# 08_USB_To_UART.net
KiCad netlist of a schematic drawn in Altium Designer
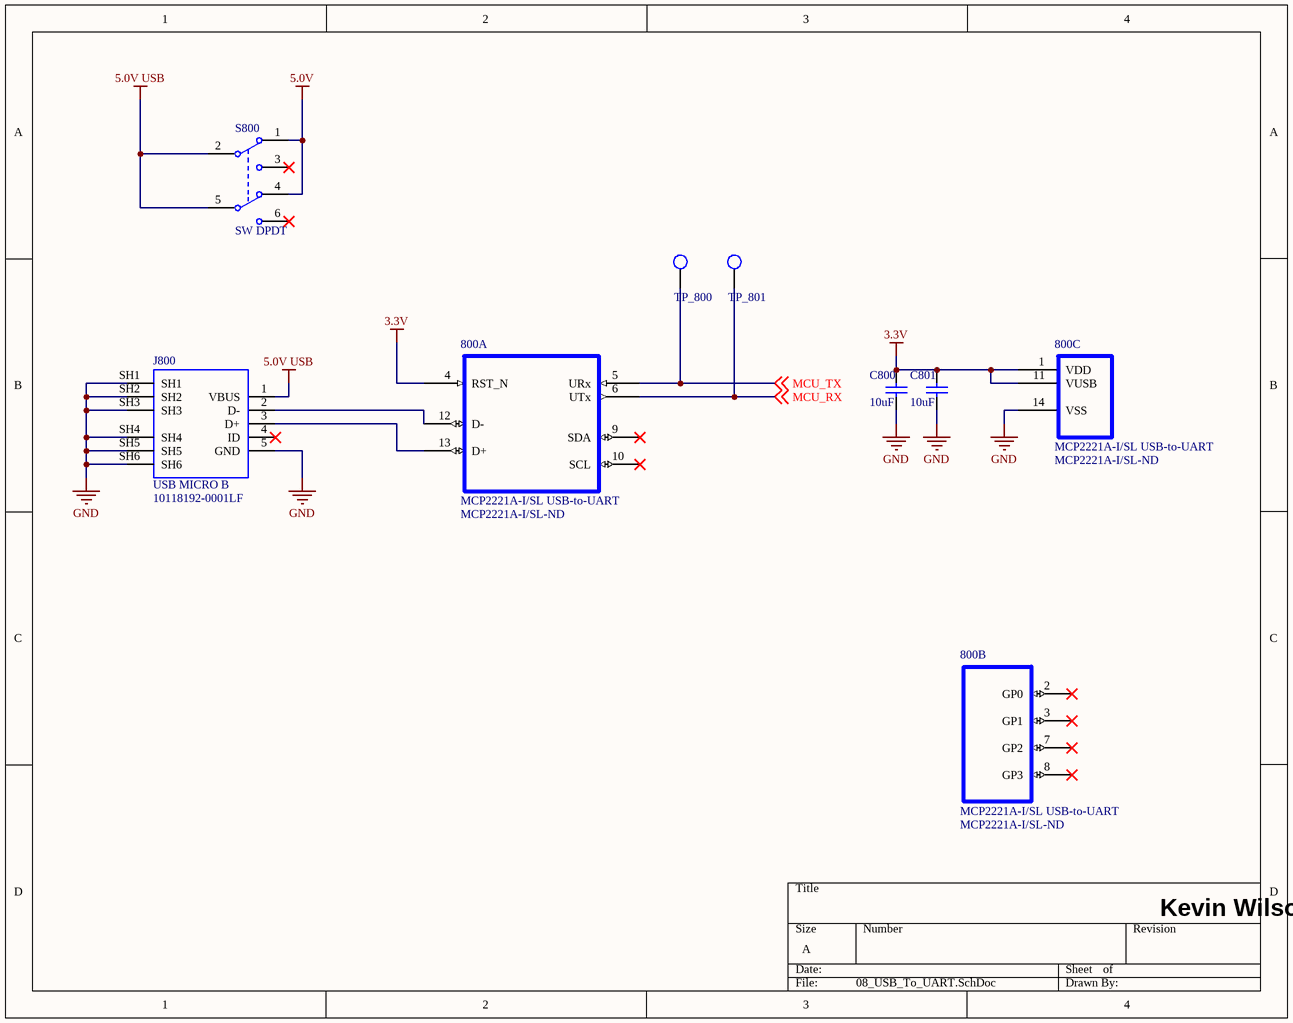
[diagram p0: 08_USB_To_UART.SchDoc]

(export (version "E")
  (design (tool "Eeschema 10.0.6"))
  (components
    (comp (ref "800")
      (value "MCP2221A-I/SL USB-to-UART")
      (footprint "IC_ MCP2221")
      (fields
        (field (name "MANUFACTURER") "Microchip")
        (field (name "MANUFACTURER PART NUMBER") "MCP2221A-I/SL")
        (field (name "SUPPLIER PART NUMBER 1") "MCP2221A-I/SL-ND")
      )
      (libsource (lib "ece315") (part "MCP2221A-I/SL USB-to-UART"))
    )
    (comp (ref "C800")
      (value "10uF")
      (footprint "CAP_0805")
      (description "CAP CER 10UF 16V X5R 0805")
      (fields
        (field (name "MANUFACTURER") "Samsung")
        (field (name "MANUFACTURER PART NUMBER") "CL21A106KOFNNNE")
      )
      (libsource (lib "ece315") (part "CAP_0805_U_010.00"))
    )
    (comp (ref "C801")
      (value "10uF")
      (footprint "CAP_0805")
      (description "CAP CER 10UF 16V X5R 0805")
      (fields
        (field (name "MANUFACTURER") "Samsung")
        (field (name "MANUFACTURER PART NUMBER") "CL21A106KOFNNNE")
      )
      (libsource (lib "ece315") (part "CAP_0805_U_010.00"))
    )
    (comp (ref "J800")
      (value "10118192-0001LF")
      (footprint "FCI_10118192")
      (description "CONN USB MICRO B RECPT SMT R/A")
      (fields
        (field (name "TOLERANCE") "USB MICRO B")
        (field (name "Comment") "CONN_RECP_FCI_10118192-0001LF.1")
      )
      (libsource (lib "ece315") (part "CONN_RECP_FCI_10118192-0001LF.1"))
    )
    (comp (ref "S800")
      (value "SW DPDT")
      (footprint "DPDT")
      (description "Switch")
      (fields
        (field (name "MANUFACTURER") "ITT /  C&K Components")
        (field (name "MANUFACTURER PART NUMBER") "JS202011SCQN")
        (field (name "PUBLISHER") "Altium Limited")
      )
      (libsource (lib "ece315") (part "SW DPDT"))
    )
    (comp (ref "TP_800")
      (value "TP_1206")
      (footprint "TP-SMC-1206")
      (description "Test Point SMD 1206")
      (fields
        (field (name "MANUFACTURER") "TE Connectivity (Tyco Electronics)")
        (field (name "MANUFACTURER PART NUMBER") "1625854-1")
      )
      (libsource (lib "ece315") (part "TP_1206"))
    )
    (comp (ref "TP_801")
      (value "TP_1206")
      (footprint "TP-SMC-1206")
      (description "Test Point SMD 1206")
      (fields
        (field (name "MANUFACTURER") "TE Connectivity (Tyco Electronics)")
        (field (name "MANUFACTURER PART NUMBER") "1625854-1")
      )
      (libsource (lib "ece315") (part "TP_1206"))
    )
  )
  (nets
    (net (code "1") (name "3.3V") (class "Default")
      (node (ref "800") (pin "1") (pinfunction "VDD_1") (pintype "power_in"))
      (node (ref "800") (pin "11") (pinfunction "VUSB_11") (pintype "power_in"))
      (node (ref "800") (pin "4") (pinfunction "RST_N_4") (pintype "input"))
      (node (ref "C800") (pin "2") (pinfunction "2_2") (pintype "passive"))
      (node (ref "C801") (pin "2") (pinfunction "2_2") (pintype "passive"))
    )
    (net (code "2") (name "5.0V") (class "Default")
      (node (ref "S800") (pin "1") (pinfunction "NC1_1") (pintype "passive"))
      (node (ref "S800") (pin "4") (pinfunction "NC2_4") (pintype "passive"))
    )
    (net (code "3") (name "5.0V USB") (class "Default")
      (node (ref "J800") (pin "1") (pinfunction "VBUS_1") (pintype "passive"))
      (node (ref "S800") (pin "2") (pinfunction "COMMON1_2") (pintype "passive"))
      (node (ref "S800") (pin "5") (pinfunction "COMMON2_5") (pintype "passive"))
    )
    (net (code "4") (name "GND") (class "Default")
      (node (ref "800") (pin "14") (pinfunction "VSS_14") (pintype "power_in"))
      (node (ref "C800") (pin "1") (pinfunction "1_1") (pintype "passive"))
      (node (ref "C801") (pin "1") (pinfunction "1_1") (pintype "passive"))
      (node (ref "J800") (pin "5") (pinfunction "GND_5") (pintype "passive"))
      (node (ref "J800") (pin "SH1") (pinfunction "SH1_SH1") (pintype "passive"))
      (node (ref "J800") (pin "SH2") (pinfunction "SH2_SH2") (pintype "passive"))
      (node (ref "J800") (pin "SH3") (pinfunction "SH3_SH3") (pintype "passive"))
      (node (ref "J800") (pin "SH4") (pinfunction "SH4_SH4") (pintype "passive"))
      (node (ref "J800") (pin "SH5") (pinfunction "SH5_SH5") (pintype "passive"))
      (node (ref "J800") (pin "SH6") (pinfunction "SH6_SH6") (pintype "passive"))
    )
    (net (code "5") (name "MCU_RX") (class "Default")
      (node (ref "800") (pin "6") (pinfunction "UTx_6") (pintype "output"))
      (node (ref "TP_801") (pin "1") (pintype "passive"))
    )
    (net (code "6") (name "MCU_TX") (class "Default")
      (node (ref "800") (pin "5") (pinfunction "URx_5") (pintype "input"))
      (node (ref "TP_800") (pin "1") (pintype "passive"))
    )
    (net (code "7") (name "Net-(800A-D+)") (class "Default")
      (node (ref "800") (pin "13") (pinfunction "D+_13") (pintype "bidirectional"))
      (node (ref "J800") (pin "3") (pinfunction "D+_3") (pintype "passive"))
    )
    (net (code "8") (name "Net-(800A-D-)") (class "Default")
      (node (ref "800") (pin "12") (pinfunction "D-_12") (pintype "bidirectional"))
      (node (ref "J800") (pin "2") (pinfunction "D-_2") (pintype "passive"))
    )
    (net (code "9") (name "unconnected-(800A-SCL-Pad10)") (class "Default")
      (node (ref "800") (pin "10") (pinfunction "SCL_10") (pintype "bidirectional+no_connect"))
    )
    (net (code "10") (name "unconnected-(800A-SDA-Pad9)") (class "Default")
      (node (ref "800") (pin "9") (pinfunction "SDA_9") (pintype "bidirectional+no_connect"))
    )
    (net (code "11") (name "unconnected-(800B-GP0-Pad2)") (class "Default")
      (node (ref "800") (pin "2") (pinfunction "GP0_2") (pintype "bidirectional+no_connect"))
    )
    (net (code "12") (name "unconnected-(800B-GP1-Pad3)") (class "Default")
      (node (ref "800") (pin "3") (pinfunction "GP1_3") (pintype "bidirectional+no_connect"))
    )
    (net (code "13") (name "unconnected-(800B-GP2-Pad7)") (class "Default")
      (node (ref "800") (pin "7") (pinfunction "GP2_7") (pintype "bidirectional+no_connect"))
    )
    (net (code "14") (name "unconnected-(800B-GP3-Pad8)") (class "Default")
      (node (ref "800") (pin "8") (pinfunction "GP3_8") (pintype "bidirectional+no_connect"))
    )
    (net (code "15") (name "unconnected-(J800-ID-Pad4)") (class "Default")
      (node (ref "J800") (pin "4") (pinfunction "ID_4") (pintype "passive+no_connect"))
    )
    (net (code "16") (name "unconnected-(S800-NO1-Pad3)") (class "Default")
      (node (ref "S800") (pin "3") (pinfunction "NO1_3") (pintype "passive+no_connect"))
    )
    (net (code "17") (name "unconnected-(S800-NO2-Pad6)") (class "Default")
      (node (ref "S800") (pin "6") (pinfunction "NO2_6") (pintype "passive+no_connect"))
    )
  )
)
